# learning_zumo.net
KiCad netlist of a schematic drawn in EAGLE
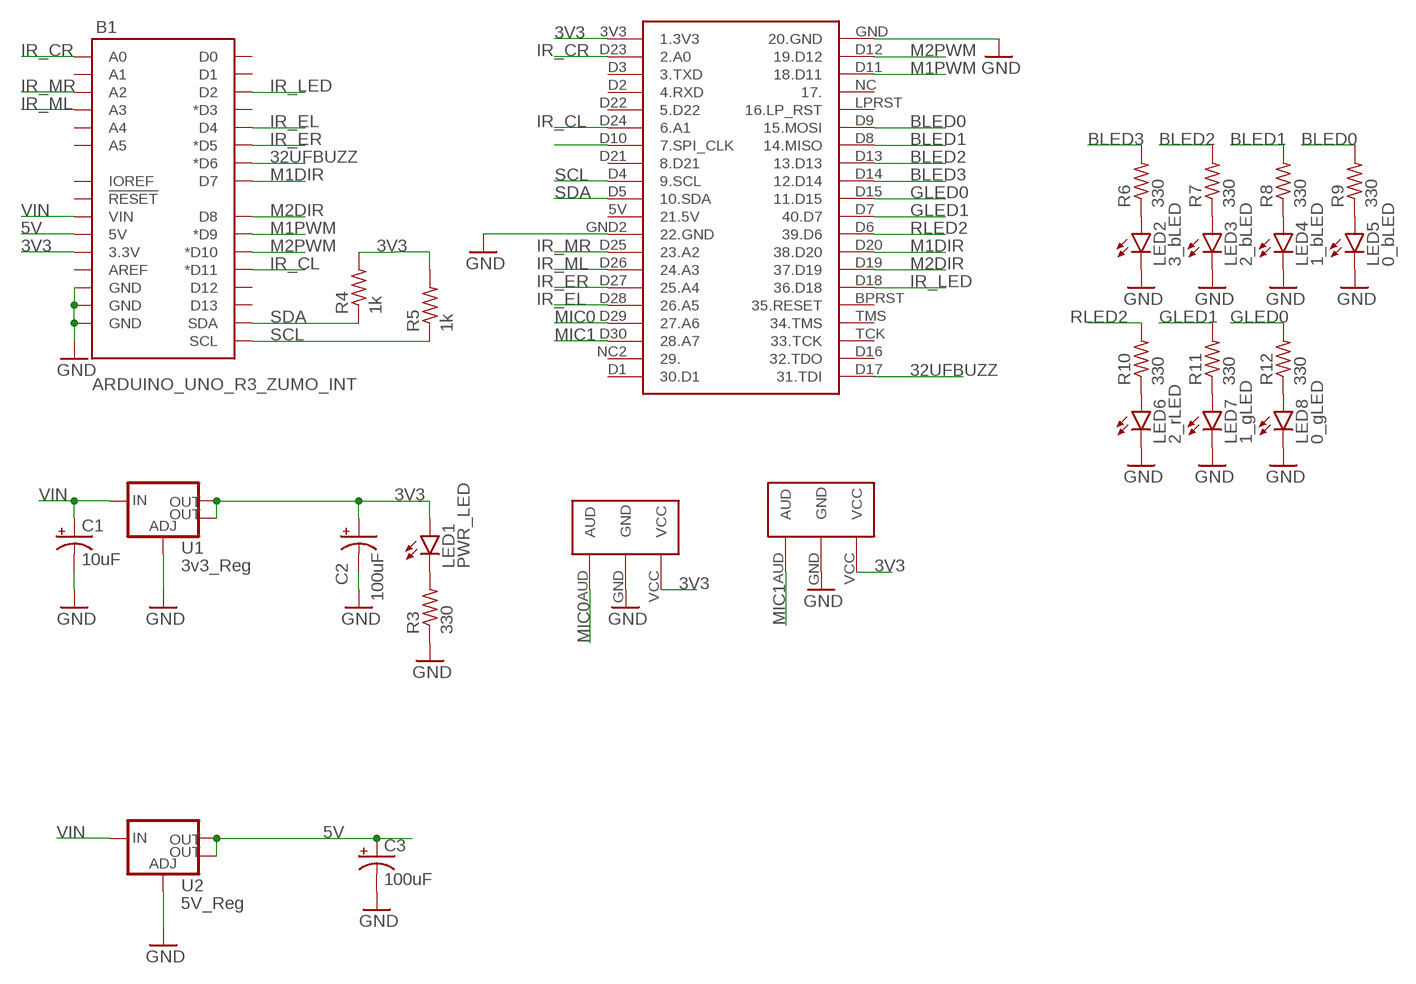
[diagram p0: schematic, sheet 1]

(export (version "E")
  (design (tool "Eeschema 10.0.6"))
  (components
    (comp (ref "B1")
      (value "ARDUINO_UNO_R3_ZUMO_INT")
      (footprint "eagle-import:UNO_R3_SHIELD_ICSP")
      (libsource (lib "eagle-import") (part "ARDUINO_UNO_R3_ZUMO_INT"))
    )
    (comp (ref "C1")
      (value "10uF")
      (footprint "eagle-import:E2,5-5")
      (libsource (lib "eagle-import") (part "CPOL-USE2.5-5"))
    )
    (comp (ref "C2")
      (value "100uF")
      (footprint "eagle-import:E2,5-5")
      (libsource (lib "eagle-import") (part "CPOL-USE2.5-5"))
    )
    (comp (ref "C3")
      (value "100uF")
      (footprint "eagle-import:E2,5-5")
      (libsource (lib "eagle-import") (part "CPOL-USE2.5-5"))
    )
    (comp (ref "LED1")
      (value "PWR_LED")
      (footprint "eagle-import:LED5MM")
      (libsource (lib "eagle-import") (part "LED5MM"))
    )
    (comp (ref "LED2")
      (value "3_bLED")
      (footprint "eagle-import:LED5MM")
      (libsource (lib "eagle-import") (part "LED5MM"))
    )
    (comp (ref "LED3")
      (value "2_bLED")
      (footprint "eagle-import:LED5MM")
      (libsource (lib "eagle-import") (part "LED5MM"))
    )
    (comp (ref "LED4")
      (value "1_bLED")
      (footprint "eagle-import:LED5MM")
      (libsource (lib "eagle-import") (part "LED5MM"))
    )
    (comp (ref "LED5")
      (value "0_bLED")
      (footprint "eagle-import:LED5MM")
      (libsource (lib "eagle-import") (part "LED5MM"))
    )
    (comp (ref "LED6")
      (value "2_rLED")
      (footprint "eagle-import:LED5MM")
      (libsource (lib "eagle-import") (part "LED5MM"))
    )
    (comp (ref "LED7")
      (value "1_gLED")
      (footprint "eagle-import:LED5MM")
      (libsource (lib "eagle-import") (part "LED5MM"))
    )
    (comp (ref "LED8")
      (value "0_gLED")
      (footprint "eagle-import:LED5MM")
      (libsource (lib "eagle-import") (part "LED5MM"))
    )
    (comp (ref "R3")
      (value "330")
      (footprint "eagle-import:0207_10")
      (libsource (lib "eagle-import") (part "R-US_0207/10"))
    )
    (comp (ref "R4")
      (value "1k")
      (footprint "eagle-import:0207_10")
      (libsource (lib "eagle-import") (part "R-US_0207/10"))
    )
    (comp (ref "R5")
      (value "1k")
      (footprint "eagle-import:0207_10")
      (libsource (lib "eagle-import") (part "R-US_0207/10"))
    )
    (comp (ref "R6")
      (value "330")
      (footprint "eagle-import:0207_10")
      (libsource (lib "eagle-import") (part "R-US_0207/10"))
    )
    (comp (ref "R7")
      (value "330")
      (footprint "eagle-import:0207_10")
      (libsource (lib "eagle-import") (part "R-US_0207/10"))
    )
    (comp (ref "R8")
      (value "330")
      (footprint "eagle-import:0207_10")
      (libsource (lib "eagle-import") (part "R-US_0207/10"))
    )
    (comp (ref "R9")
      (value "330")
      (footprint "eagle-import:0207_10")
      (libsource (lib "eagle-import") (part "R-US_0207/10"))
    )
    (comp (ref "R10")
      (value "330")
      (footprint "eagle-import:0207_10")
      (libsource (lib "eagle-import") (part "R-US_0207/10"))
    )
    (comp (ref "R11")
      (value "330")
      (footprint "eagle-import:0207_10")
      (libsource (lib "eagle-import") (part "R-US_0207/10"))
    )
    (comp (ref "R12")
      (value "330")
      (footprint "eagle-import:0207_10")
      (libsource (lib "eagle-import") (part "R-US_0207/10"))
    )
    (comp (ref "U$1")
      (value "CC1310_INT")
      (footprint "eagle-import:CC1310_INT")
      (libsource (lib "eagle-import") (part "CC1310_INT"))
    )
    (comp (ref "U$2")
      (value "ANALOG_MIC")
      (footprint "eagle-import:ANALOG_MIC")
      (libsource (lib "eagle-import") (part "ANALOG_MIC"))
    )
    (comp (ref "U$3")
      (value "ANALOG_MIC")
      (footprint "eagle-import:ANALOG_MIC")
      (libsource (lib "eagle-import") (part "ANALOG_MIC"))
    )
    (comp (ref "U1")
      (value "3v3_Reg")
      (footprint "eagle-import:NU32V7_SOT223")
      (libsource (lib "eagle-import") (part "NU32V7_V_REG_LM1117SOT223"))
    )
    (comp (ref "U2")
      (value "5V_Reg")
      (footprint "eagle-import:NU32V7_SOT223")
      (libsource (lib "eagle-import") (part "NU32V7_V_REG_LM1117SOT223"))
    )
  )
  (nets
    (net (code "1") (name "/3V3") (class "Default")
      (node (ref "B1") (pin "3.3V") (pinfunction "3.3V_3.3V") (pintype "bidirectional"))
      (node (ref "C2") (pin "+") (pinfunction "+_+") (pintype "passive"))
      (node (ref "LED1") (pin "A") (pinfunction "A_A") (pintype "passive"))
      (node (ref "R4") (pin "2") (pinfunction "2_2") (pintype "passive"))
      (node (ref "R5") (pin "2") (pinfunction "2_2") (pintype "passive"))
      (node (ref "U$1") (pin "3V3") (pinfunction "1.3V3_3V3") (pintype "bidirectional"))
      (node (ref "U$2") (pin "VCC") (pinfunction "VCC_VCC") (pintype "bidirectional"))
      (node (ref "U$3") (pin "VCC") (pinfunction "VCC_VCC") (pintype "bidirectional"))
      (node (ref "U1") (pin "OUTPUT") (pinfunction "OUT_OUTPUT") (pintype "output"))
      (node (ref "U1") (pin "VOUT") (pinfunction "OUT_VOUT") (pintype "output"))
    )
    (net (code "2") (name "/5V") (class "Default")
      (node (ref "B1") (pin "5V") (pinfunction "5V_5V") (pintype "bidirectional"))
      (node (ref "C3") (pin "+") (pinfunction "+_+") (pintype "passive"))
      (node (ref "U2") (pin "OUTPUT") (pinfunction "OUT_OUTPUT") (pintype "output"))
      (node (ref "U2") (pin "VOUT") (pinfunction "OUT_VOUT") (pintype "output"))
    )
    (net (code "3") (name "/32UFBUZZ") (class "Default")
      (node (ref "B1") (pin "D6") (pinfunction "*D6_D6") (pintype "bidirectional"))
      (node (ref "U$1") (pin "D17") (pinfunction "31.TDI_D17") (pintype "bidirectional"))
    )
    (net (code "4") (name "/BLED0") (class "Default")
      (node (ref "R9") (pin "2") (pinfunction "2_2") (pintype "passive"))
      (node (ref "U$1") (pin "D9") (pinfunction "15.MOSI_D9") (pintype "bidirectional"))
    )
    (net (code "5") (name "/BLED1") (class "Default")
      (node (ref "R8") (pin "2") (pinfunction "2_2") (pintype "passive"))
      (node (ref "U$1") (pin "D8") (pinfunction "14.MISO_D8") (pintype "bidirectional"))
    )
    (net (code "6") (name "/BLED2") (class "Default")
      (node (ref "R7") (pin "2") (pinfunction "2_2") (pintype "passive"))
      (node (ref "U$1") (pin "D13") (pinfunction "13.D13_D13") (pintype "bidirectional"))
    )
    (net (code "7") (name "/BLED3") (class "Default")
      (node (ref "R6") (pin "2") (pinfunction "2_2") (pintype "passive"))
      (node (ref "U$1") (pin "D14") (pinfunction "12.D14_D14") (pintype "bidirectional"))
    )
    (net (code "8") (name "/GLED0") (class "Default")
      (node (ref "R12") (pin "2") (pinfunction "2_2") (pintype "passive"))
      (node (ref "U$1") (pin "D15") (pinfunction "11.D15_D15") (pintype "bidirectional"))
    )
    (net (code "9") (name "/GLED1") (class "Default")
      (node (ref "R11") (pin "2") (pinfunction "2_2") (pintype "passive"))
      (node (ref "U$1") (pin "D7") (pinfunction "40.D7_D7") (pintype "bidirectional"))
    )
    (net (code "10") (name "/IR_CL") (class "Default")
      (node (ref "B1") (pin "D11") (pinfunction "*D11_D11") (pintype "bidirectional"))
      (node (ref "U$1") (pin "D24") (pinfunction "6.A1_D24") (pintype "bidirectional"))
    )
    (net (code "11") (name "/IR_CR") (class "Default")
      (node (ref "B1") (pin "A0") (pinfunction "A0_A0") (pintype "bidirectional"))
      (node (ref "U$1") (pin "D23") (pinfunction "2.A0_D23") (pintype "bidirectional"))
    )
    (net (code "12") (name "/IR_EL") (class "Default")
      (node (ref "B1") (pin "D4") (pinfunction "D4_D4") (pintype "bidirectional"))
      (node (ref "U$1") (pin "D28") (pinfunction "26.A5_D28") (pintype "bidirectional"))
    )
    (net (code "13") (name "/IR_ER") (class "Default")
      (node (ref "B1") (pin "D5") (pinfunction "*D5_D5") (pintype "bidirectional"))
      (node (ref "U$1") (pin "D27") (pinfunction "25.A4_D27") (pintype "bidirectional"))
    )
    (net (code "14") (name "/IR_LED") (class "Default")
      (node (ref "B1") (pin "D2") (pinfunction "D2_D2") (pintype "bidirectional"))
      (node (ref "U$1") (pin "D18") (pinfunction "36.D18_D18") (pintype "bidirectional"))
    )
    (net (code "15") (name "/IR_ML") (class "Default")
      (node (ref "B1") (pin "A3") (pinfunction "A3_A3") (pintype "bidirectional"))
      (node (ref "U$1") (pin "D26") (pinfunction "24.A3_D26") (pintype "bidirectional"))
    )
    (net (code "16") (name "/IR_MR") (class "Default")
      (node (ref "B1") (pin "A2") (pinfunction "A2_A2") (pintype "bidirectional"))
      (node (ref "U$1") (pin "D25") (pinfunction "23.A2_D25") (pintype "bidirectional"))
    )
    (net (code "17") (name "/M1DIR") (class "Default")
      (node (ref "B1") (pin "D7") (pinfunction "D7_D7") (pintype "bidirectional"))
      (node (ref "U$1") (pin "D20") (pinfunction "38.D20_D20") (pintype "bidirectional"))
    )
    (net (code "18") (name "/M1PWM") (class "Default")
      (node (ref "B1") (pin "D9") (pinfunction "*D9_D9") (pintype "bidirectional"))
      (node (ref "U$1") (pin "D11") (pinfunction "18.D11_D11") (pintype "bidirectional"))
    )
    (net (code "19") (name "/M2DIR") (class "Default")
      (node (ref "B1") (pin "D8") (pinfunction "D8_D8") (pintype "bidirectional"))
      (node (ref "U$1") (pin "D19") (pinfunction "37.D19_D19") (pintype "bidirectional"))
    )
    (net (code "20") (name "/M2PWM") (class "Default")
      (node (ref "B1") (pin "D10") (pinfunction "*D10_D10") (pintype "bidirectional"))
      (node (ref "U$1") (pin "D12") (pinfunction "19.D12_D12") (pintype "bidirectional"))
    )
    (net (code "21") (name "/MIC0") (class "Default")
      (node (ref "U$1") (pin "D29") (pinfunction "27.A6_D29") (pintype "bidirectional"))
      (node (ref "U$2") (pin "AUD") (pinfunction "AUD_AUD") (pintype "bidirectional"))
    )
    (net (code "22") (name "/MIC1") (class "Default")
      (node (ref "U$1") (pin "D30") (pinfunction "28.A7_D30") (pintype "bidirectional"))
      (node (ref "U$3") (pin "AUD") (pinfunction "AUD_AUD") (pintype "bidirectional"))
    )
    (net (code "23") (name "/RLED2") (class "Default")
      (node (ref "R10") (pin "2") (pinfunction "2_2") (pintype "passive"))
      (node (ref "U$1") (pin "D6") (pinfunction "39.D6_D6") (pintype "bidirectional"))
    )
    (net (code "24") (name "/SCL") (class "Default")
      (node (ref "B1") (pin "SCL") (pinfunction "SCL_SCL") (pintype "bidirectional"))
      (node (ref "R5") (pin "1") (pinfunction "1_1") (pintype "passive"))
      (node (ref "U$1") (pin "D4") (pinfunction "9.SCL_D4") (pintype "bidirectional"))
    )
    (net (code "25") (name "/SDA") (class "Default")
      (node (ref "B1") (pin "SDA") (pinfunction "SDA_SDA") (pintype "bidirectional"))
      (node (ref "R4") (pin "1") (pinfunction "1_1") (pintype "passive"))
      (node (ref "U$1") (pin "D5") (pinfunction "10.SDA_D5") (pintype "bidirectional"))
    )
    (net (code "26") (name "/VIN") (class "Default")
      (node (ref "B1") (pin "VIN") (pinfunction "VIN_VIN") (pintype "bidirectional"))
      (node (ref "C1") (pin "+") (pinfunction "+_+") (pintype "passive"))
      (node (ref "U1") (pin "INPUT") (pinfunction "IN_INPUT") (pintype "input"))
      (node (ref "U2") (pin "INPUT") (pinfunction "IN_INPUT") (pintype "input"))
    )
    (net (code "27") (name "GND") (class "Default")
      (node (ref "B1") (pin "GND@0") (pinfunction "GND_GND@0") (pintype "bidirectional"))
      (node (ref "B1") (pin "GND@1") (pinfunction "GND_GND@1") (pintype "bidirectional"))
      (node (ref "B1") (pin "GND@2") (pinfunction "GND_GND@2") (pintype "bidirectional"))
      (node (ref "C1") (pin "-") (pinfunction "-_-") (pintype "passive"))
      (node (ref "C2") (pin "-") (pinfunction "-_-") (pintype "passive"))
      (node (ref "C3") (pin "-") (pinfunction "-_-") (pintype "passive"))
      (node (ref "LED2") (pin "K") (pinfunction "C_K") (pintype "passive"))
      (node (ref "LED3") (pin "K") (pinfunction "C_K") (pintype "passive"))
      (node (ref "LED4") (pin "K") (pinfunction "C_K") (pintype "passive"))
      (node (ref "LED5") (pin "K") (pinfunction "C_K") (pintype "passive"))
      (node (ref "LED6") (pin "K") (pinfunction "C_K") (pintype "passive"))
      (node (ref "LED7") (pin "K") (pinfunction "C_K") (pintype "passive"))
      (node (ref "LED8") (pin "K") (pinfunction "C_K") (pintype "passive"))
      (node (ref "R3") (pin "1") (pinfunction "1_1") (pintype "passive"))
      (node (ref "U$1") (pin "GND") (pinfunction "20.GND_GND") (pintype "bidirectional"))
      (node (ref "U$1") (pin "GND2") (pinfunction "22.GND_GND2") (pintype "bidirectional"))
      (node (ref "U$2") (pin "GND") (pinfunction "GND_GND") (pintype "bidirectional"))
      (node (ref "U$3") (pin "GND") (pinfunction "GND_GND") (pintype "bidirectional"))
      (node (ref "U1") (pin "GND") (pinfunction "ADJ_GND") (pintype "input"))
      (node (ref "U2") (pin "GND") (pinfunction "ADJ_GND") (pintype "input"))
    )
    (net (code "28") (name "Net-(LED1-C)") (class "Default")
      (node (ref "LED1") (pin "K") (pinfunction "C_K") (pintype "passive"))
      (node (ref "R3") (pin "2") (pinfunction "2_2") (pintype "passive"))
    )
    (net (code "29") (name "Net-(LED2-PadA)") (class "Default")
      (node (ref "LED2") (pin "A") (pinfunction "A_A") (pintype "passive"))
      (node (ref "R6") (pin "1") (pinfunction "1_1") (pintype "passive"))
    )
    (net (code "30") (name "Net-(LED3-PadA)") (class "Default")
      (node (ref "LED3") (pin "A") (pinfunction "A_A") (pintype "passive"))
      (node (ref "R7") (pin "1") (pinfunction "1_1") (pintype "passive"))
    )
    (net (code "31") (name "Net-(LED4-PadA)") (class "Default")
      (node (ref "LED4") (pin "A") (pinfunction "A_A") (pintype "passive"))
      (node (ref "R8") (pin "1") (pinfunction "1_1") (pintype "passive"))
    )
    (net (code "32") (name "Net-(LED5-PadA)") (class "Default")
      (node (ref "LED5") (pin "A") (pinfunction "A_A") (pintype "passive"))
      (node (ref "R9") (pin "1") (pinfunction "1_1") (pintype "passive"))
    )
    (net (code "33") (name "Net-(LED6-PadA)") (class "Default")
      (node (ref "LED6") (pin "A") (pinfunction "A_A") (pintype "passive"))
      (node (ref "R10") (pin "1") (pinfunction "1_1") (pintype "passive"))
    )
    (net (code "34") (name "Net-(LED7-PadA)") (class "Default")
      (node (ref "LED7") (pin "A") (pinfunction "A_A") (pintype "passive"))
      (node (ref "R11") (pin "1") (pinfunction "1_1") (pintype "passive"))
    )
    (net (code "35") (name "Net-(LED8-PadA)") (class "Default")
      (node (ref "LED8") (pin "A") (pinfunction "A_A") (pintype "passive"))
      (node (ref "R12") (pin "1") (pinfunction "1_1") (pintype "passive"))
    )
    (net (code "36") (name "unconnected-(B1-*D3-PadD3)") (class "Default")
      (node (ref "B1") (pin "D3") (pinfunction "*D3_D3") (pintype "bidirectional"))
    )
    (net (code "37") (name "unconnected-(B1-D0-PadRX)") (class "Default")
      (node (ref "B1") (pin "RX") (pinfunction "D0_RX") (pintype "bidirectional"))
    )
    (net (code "38") (name "unconnected-(B1-D1-PadTX)") (class "Default")
      (node (ref "B1") (pin "TX") (pinfunction "D1_TX") (pintype "bidirectional"))
    )
    (net (code "39") (name "unconnected-(B1-PadA1)") (class "Default")
      (node (ref "B1") (pin "A1") (pinfunction "A1_A1") (pintype "bidirectional"))
    )
    (net (code "40") (name "unconnected-(B1-PadA4)") (class "Default")
      (node (ref "B1") (pin "A4") (pinfunction "A4_A4") (pintype "bidirectional"))
    )
    (net (code "41") (name "unconnected-(B1-PadA5)") (class "Default")
      (node (ref "B1") (pin "A5") (pinfunction "A5_A5") (pintype "bidirectional"))
    )
    (net (code "42") (name "unconnected-(B1-PadAREF)") (class "Default")
      (node (ref "B1") (pin "AREF") (pinfunction "AREF_AREF") (pintype "bidirectional"))
    )
    (net (code "43") (name "unconnected-(B1-PadD12)") (class "Default")
      (node (ref "B1") (pin "D12") (pinfunction "D12_D12") (pintype "bidirectional"))
    )
    (net (code "44") (name "unconnected-(B1-PadD13)") (class "Default")
      (node (ref "B1") (pin "D13") (pinfunction "D13_D13") (pintype "bidirectional"))
    )
    (net (code "45") (name "unconnected-(B1-PadIOREF)") (class "Default")
      (node (ref "B1") (pin "IOREF") (pinfunction "IOREF_IOREF") (pintype "bidirectional"))
    )
    (net (code "46") (name "unconnected-(B1-~{RESET}-PadRES)") (class "Default")
      (node (ref "B1") (pin "RES") (pinfunction "~{RESET}_RES") (pintype "bidirectional"))
    )
    (net (code "47") (name "unconnected-(U$1-3.TXD-PadD3)") (class "Default")
      (node (ref "U$1") (pin "D3") (pinfunction "3.TXD_D3") (pintype "bidirectional"))
    )
    (net (code "48") (name "unconnected-(U$1-4.RXD-PadD2)") (class "Default")
      (node (ref "U$1") (pin "D2") (pinfunction "4.RXD_D2") (pintype "bidirectional"))
    )
    (net (code "49") (name "unconnected-(U$1-5.D22-PadD22)") (class "Default")
      (node (ref "U$1") (pin "D22") (pinfunction "5.D22_D22") (pintype "bidirectional"))
    )
    (net (code "50") (name "unconnected-(U$1-7.SPI_CLK-PadD10)") (class "Default")
      (node (ref "U$1") (pin "D10") (pinfunction "7.SPI_CLK_D10") (pintype "bidirectional"))
    )
    (net (code "51") (name "unconnected-(U$1-8.D21-PadD21)") (class "Default")
      (node (ref "U$1") (pin "D21") (pinfunction "8.D21_D21") (pintype "bidirectional"))
    )
    (net (code "52") (name "unconnected-(U$1-16.LP_RST-PadLPRST)") (class "Default")
      (node (ref "U$1") (pin "LPRST") (pinfunction "16.LP_RST_LPRST") (pintype "bidirectional"))
    )
    (net (code "53") (name "unconnected-(U$1-17.-PadNC)") (class "Default")
      (node (ref "U$1") (pin "NC") (pinfunction "17._NC") (pintype "bidirectional"))
    )
    (net (code "54") (name "unconnected-(U$1-21.5V-Pad5V)") (class "Default")
      (node (ref "U$1") (pin "5V") (pinfunction "21.5V_5V") (pintype "bidirectional"))
    )
    (net (code "55") (name "unconnected-(U$1-29.-PadNC2)") (class "Default")
      (node (ref "U$1") (pin "NC2") (pinfunction "29._NC2") (pintype "bidirectional"))
    )
    (net (code "56") (name "unconnected-(U$1-30.D1-PadD1)") (class "Default")
      (node (ref "U$1") (pin "D1") (pinfunction "30.D1_D1") (pintype "bidirectional"))
    )
    (net (code "57") (name "unconnected-(U$1-32.TDO-PadD16)") (class "Default")
      (node (ref "U$1") (pin "D16") (pinfunction "32.TDO_D16") (pintype "bidirectional"))
    )
    (net (code "58") (name "unconnected-(U$1-33.TCK-PadTCK)") (class "Default")
      (node (ref "U$1") (pin "TCK") (pinfunction "33.TCK_TCK") (pintype "bidirectional"))
    )
    (net (code "59") (name "unconnected-(U$1-34.TMS-PadTMS)") (class "Default")
      (node (ref "U$1") (pin "TMS") (pinfunction "34.TMS_TMS") (pintype "bidirectional"))
    )
    (net (code "60") (name "unconnected-(U$1-35.RESET-PadBPRST)") (class "Default")
      (node (ref "U$1") (pin "BPRST") (pinfunction "35.RESET_BPRST") (pintype "bidirectional"))
    )
  )
)
